# 08_Parallel_operation.net
KiCad netlist of a schematic drawn in Altium Designer
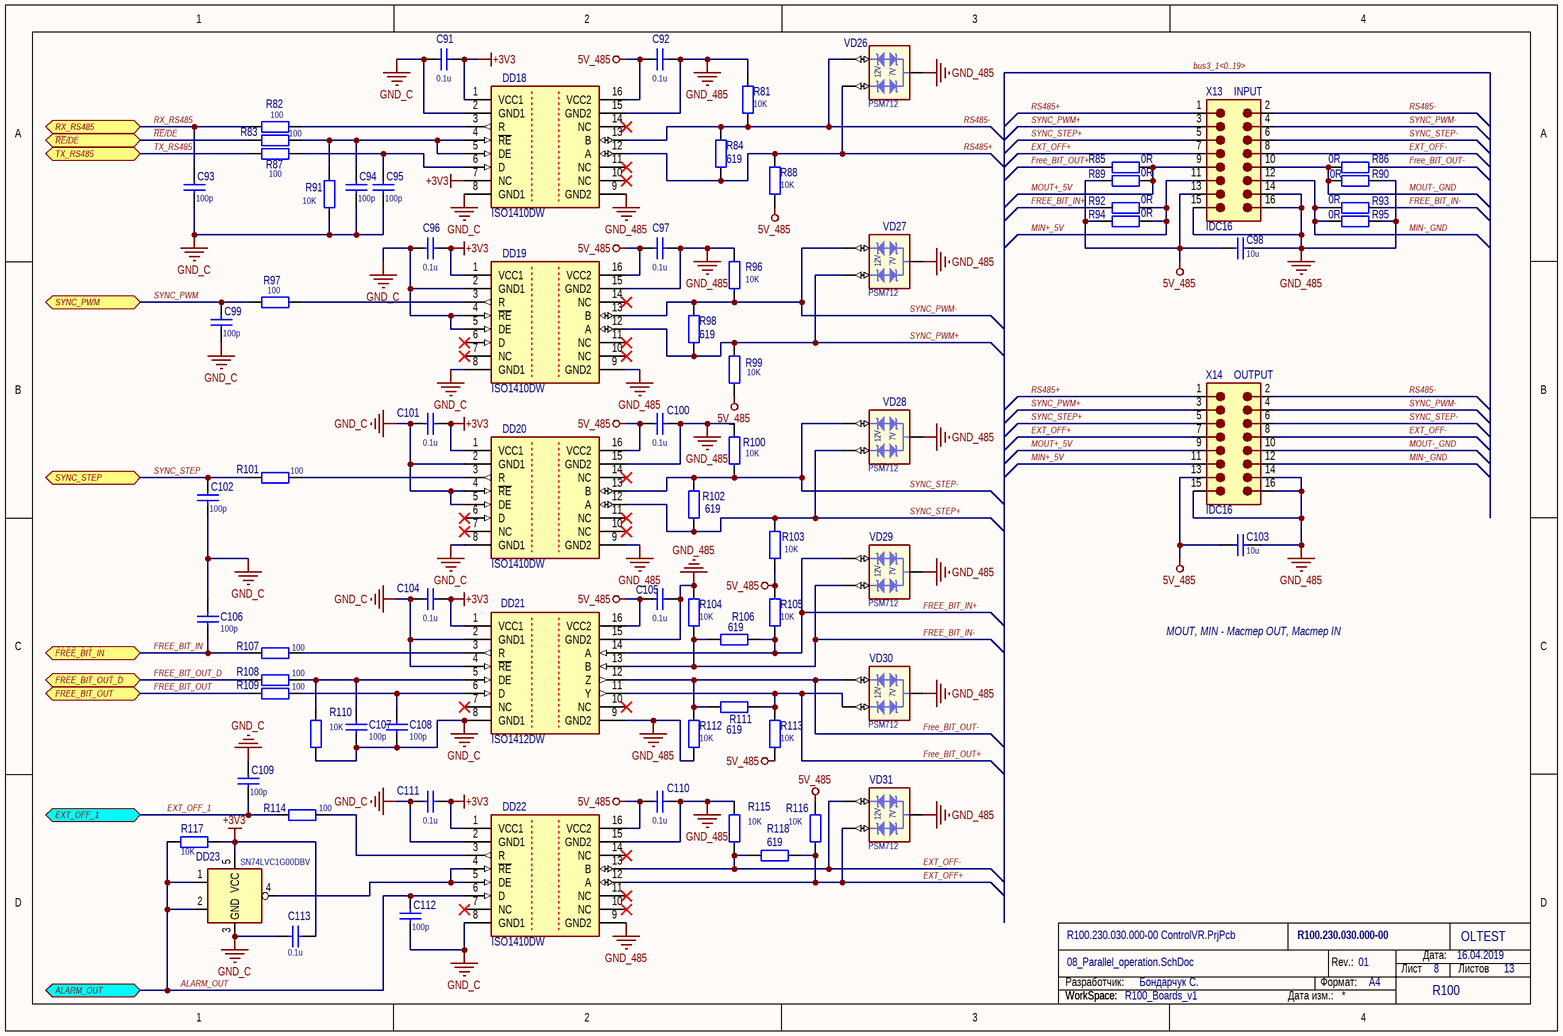
[diagram p0: 08_Parallel_operation.SchDoc]

(export (version "E")
  (design (tool "Eeschema 10.0.6"))
  (components
    (comp (ref "C91")
      (value "0.1u")
      (footprint "mainLib:SMD_C_0603")
      (description "SMD C 0603 MURATA 50V 10% X7R")
      (fields (field (name "PARTNUMBER") "GRM188R71H104K") (field (name "MANUFACTURER") "MURATA"))
      (libsource (lib "mainRCLib") (part "C0603 0.1u 50V 10%"))
    )
    (comp (ref "C92")
      (value "0.1u")
      (footprint "mainLib:SMD_C_0603")
      (description "SMD C 0603 MURATA 50V 10% X7R")
      (fields (field (name "PARTNUMBER") "GRM188R71H104K") (field (name "MANUFACTURER") "MURATA"))
      (libsource (lib "mainRCLib") (part "C0603 0.1u 50V 10%"))
    )
    (comp (ref "C93")
      (value "100p")
      (footprint "mainLib:SMD_C_0603")
      (description "SMD C 0603 MURATA 100V 5% NP0")
      (fields (field (name "PARTNUMBER") "GRM1885C2A101JA01") (field (name "MANUFACTURER") "MURATA"))
      (libsource (lib "mainRCLib") (part "C0603 100p 100V 5%"))
    )
    (comp (ref "C94")
      (value "100p")
      (footprint "mainLib:SMD_C_0603")
      (description "SMD C 0603 MURATA 100V 5% NP0")
      (fields (field (name "PARTNUMBER") "GRM1885C2A101JA01") (field (name "MANUFACTURER") "MURATA"))
      (libsource (lib "mainRCLib") (part "C0603 100p 100V 5%"))
    )
    (comp (ref "C95")
      (value "100p")
      (footprint "mainLib:SMD_C_0603")
      (description "SMD C 0603 MURATA 100V 5% NP0")
      (fields (field (name "PARTNUMBER") "GRM1885C2A101JA01") (field (name "MANUFACTURER") "MURATA"))
      (libsource (lib "mainRCLib") (part "C0603 100p 100V 5%"))
    )
    (comp (ref "C96")
      (value "0.1u")
      (footprint "mainLib:SMD_C_0603")
      (description "SMD C 0603 MURATA 50V 10% X7R")
      (fields (field (name "PARTNUMBER") "GRM188R71H104K") (field (name "MANUFACTURER") "MURATA"))
      (libsource (lib "mainRCLib") (part "C0603 0.1u 50V 10%"))
    )
    (comp (ref "C97")
      (value "0.1u")
      (footprint "mainLib:SMD_C_0603")
      (description "SMD C 0603 MURATA 50V 10% X7R")
      (fields (field (name "PARTNUMBER") "GRM188R71H104K") (field (name "MANUFACTURER") "MURATA"))
      (libsource (lib "mainRCLib") (part "C0603 0.1u 50V 10%"))
    )
    (comp (ref "C98")
      (value "10u")
      (footprint "mainLib:SMD_C_1206")
      (description "SMD C 1206 MURATA 25V 20% X5R")
      (fields (field (name "PARTNUMBER") "GRM31MR61E106M") (field (name "MANUFACTURER") "MURATA"))
      (libsource (lib "mainRCLib") (part "C1206 10u 25V 20%"))
    )
    (comp (ref "C99")
      (value "100p")
      (footprint "mainLib:SMD_C_0603")
      (description "SMD C 0603 MURATA 100V 5% NP0")
      (fields (field (name "PARTNUMBER") "GRM1885C2A101JA01") (field (name "MANUFACTURER") "MURATA"))
      (libsource (lib "mainRCLib") (part "C0603 100p 100V 5%"))
    )
    (comp (ref "C100")
      (value "0.1u")
      (footprint "mainLib:SMD_C_0603")
      (description "SMD C 0603 MURATA 50V 10% X7R")
      (fields (field (name "PARTNUMBER") "GRM188R71H104K") (field (name "MANUFACTURER") "MURATA"))
      (libsource (lib "mainRCLib") (part "C0603 0.1u 50V 10%"))
    )
    (comp (ref "C101")
      (value "0.1u")
      (footprint "mainLib:SMD_C_0603")
      (description "SMD C 0603 MURATA 50V 10% X7R")
      (fields (field (name "PARTNUMBER") "GRM188R71H104K") (field (name "MANUFACTURER") "MURATA"))
      (libsource (lib "mainRCLib") (part "C0603 0.1u 50V 10%"))
    )
    (comp (ref "C102")
      (value "100p")
      (footprint "mainLib:SMD_C_0603")
      (description "SMD C 0603 MURATA 100V 5% NP0")
      (fields (field (name "PARTNUMBER") "GRM1885C2A101JA01") (field (name "MANUFACTURER") "MURATA"))
      (libsource (lib "mainRCLib") (part "C0603 100p 100V 5%"))
    )
    (comp (ref "C103")
      (value "10u")
      (footprint "mainLib:SMD_C_1206")
      (description "SMD C 1206 MURATA 25V 20% X5R")
      (fields (field (name "PARTNUMBER") "GRM31MR61E106M") (field (name "MANUFACTURER") "MURATA"))
      (libsource (lib "mainRCLib") (part "C1206 10u 25V 20%"))
    )
    (comp (ref "C104")
      (value "0.1u")
      (footprint "mainLib:SMD_C_0603")
      (description "SMD C 0603 MURATA 50V 10% X7R")
      (fields (field (name "PARTNUMBER") "GRM188R71H104K") (field (name "MANUFACTURER") "MURATA"))
      (libsource (lib "mainRCLib") (part "C0603 0.1u 50V 10%"))
    )
    (comp (ref "C105")
      (value "0.1u")
      (footprint "mainLib:SMD_C_0603")
      (description "SMD C 0603 MURATA 50V 10% X7R")
      (fields (field (name "PARTNUMBER") "GRM188R71H104K") (field (name "MANUFACTURER") "MURATA"))
      (libsource (lib "mainRCLib") (part "C0603 0.1u 50V 10%"))
    )
    (comp (ref "C106")
      (value "100p")
      (footprint "mainLib:SMD_C_0603")
      (description "SMD C 0603 MURATA 100V 5% NP0")
      (fields (field (name "PARTNUMBER") "GRM1885C2A101JA01") (field (name "MANUFACTURER") "MURATA"))
      (libsource (lib "mainRCLib") (part "C0603 100p 100V 5%"))
    )
    (comp (ref "C107")
      (value "100p")
      (footprint "mainLib:SMD_C_0603")
      (description "SMD C 0603 MURATA 100V 5% NP0")
      (fields (field (name "PARTNUMBER") "GRM1885C2A101JA01") (field (name "MANUFACTURER") "MURATA"))
      (libsource (lib "mainRCLib") (part "C0603 100p 100V 5%"))
    )
    (comp (ref "C108")
      (value "100p")
      (footprint "mainLib:SMD_C_0603")
      (description "SMD C 0603 MURATA 100V 5% NP0")
      (fields (field (name "PARTNUMBER") "GRM1885C2A101JA01") (field (name "MANUFACTURER") "MURATA"))
      (libsource (lib "mainRCLib") (part "C0603 100p 100V 5%"))
    )
    (comp (ref "C109")
      (value "100p")
      (footprint "mainLib:SMD_C_0603")
      (description "SMD C 0603 MURATA 100V 5% NP0")
      (fields (field (name "PARTNUMBER") "GRM1885C2A101JA01") (field (name "MANUFACTURER") "MURATA"))
      (libsource (lib "mainRCLib") (part "C0603 100p 100V 5%"))
    )
    (comp (ref "C110")
      (value "0.1u")
      (footprint "mainLib:SMD_C_0603")
      (description "SMD C 0603 MURATA 50V 10% X7R")
      (fields (field (name "PARTNUMBER") "GRM188R71H104K") (field (name "MANUFACTURER") "MURATA"))
      (libsource (lib "mainRCLib") (part "C0603 0.1u 50V 10%"))
    )
    (comp (ref "C111")
      (value "0.1u")
      (footprint "mainLib:SMD_C_0603")
      (description "SMD C 0603 MURATA 50V 10% X7R")
      (fields (field (name "PARTNUMBER") "GRM188R71H104K") (field (name "MANUFACTURER") "MURATA"))
      (libsource (lib "mainRCLib") (part "C0603 0.1u 50V 10%"))
    )
    (comp (ref "C112")
      (value "100p")
      (footprint "mainLib:SMD_C_0603")
      (description "SMD C 0603 MURATA 100V 5% NP0")
      (fields (field (name "PARTNUMBER") "GRM1885C2A101JA01") (field (name "MANUFACTURER") "MURATA"))
      (libsource (lib "mainRCLib") (part "C0603 100p 100V 5%"))
    )
    (comp (ref "C113")
      (value "0.1u")
      (footprint "mainLib:SMD_C_0603")
      (description "SMD C 0603 MURATA 50V 10% X7R")
      (fields (field (name "PARTNUMBER") "GRM188R71H104K") (field (name "MANUFACTURER") "MURATA"))
      (libsource (lib "mainRCLib") (part "C0603 0.1u 50V 10%"))
    )
    (comp (ref "DD18")
      (value "ISO1410DW")
      (footprint "mainLib:SOIC127P1030X265-16M")
      (description "Isolated, Half-Dupl RS-485 Transiver")
      (fields (field (name "MANUFACTURER") "Texas Instrument"))
      (libsource (lib "mainLib") (part "ISO1410DW"))
    )
    (comp (ref "DD19")
      (value "ISO1410DW")
      (footprint "mainLib:SOIC127P1030X265-16M")
      (description "Isolated, Half-Dupl RS-485 Transiver")
      (fields (field (name "MANUFACTURER") "Texas Instrument"))
      (libsource (lib "mainLib") (part "ISO1410DW"))
    )
    (comp (ref "DD20")
      (value "ISO1410DW")
      (footprint "mainLib:SOIC127P1030X265-16M")
      (description "Isolated, Half-Dupl RS-485 Transiver")
      (fields (field (name "MANUFACTURER") "Texas Instrument"))
      (libsource (lib "mainLib") (part "ISO1410DW"))
    )
    (comp (ref "DD21")
      (value "ISO1412DW")
      (footprint "mainLib:SOIC127P1030X265-16M")
      (description "Isolated, Full-Dupl RS-485 Transiver")
      (fields (field (name "MANUFACTURER") "Texas Instrument"))
      (libsource (lib "mainLib") (part "ISO1412DW"))
    )
    (comp (ref "DD22")
      (value "ISO1410DW")
      (footprint "mainLib:SOIC127P1030X265-16M")
      (description "Isolated, Half-Dupl RS-485 Transiver")
      (fields (field (name "MANUFACTURER") "Texas Instrument"))
      (libsource (lib "mainLib") (part "ISO1410DW"))
    )
    (comp (ref "DD23")
      (value "SN74LVC1G00DBV")
      (footprint "mainLib:SOT-23(DBV)")
      (description "2-in NAND")
      (fields (field (name "MANUFACTURER") "Texas Instruments"))
      (libsource (lib "mainLib") (part "SN74LVC1G00DBV"))
    )
    (comp (ref "R81")
      (value "10K")
      (footprint "SMD_R_0603")
      (description "SMD R 0603 VISHAY 0.1W 75V 1% 100ppm")
      (fields (field (name "PARTNUMBER") "CRCW060310K0FK") (field (name "MANUFACTURER") "VISHAY"))
      (libsource (lib "") (part "R0603 10К 1%_1"))
    )
    (comp (ref "R82")
      (value "100")
      (footprint "SMD_R_0603")
      (description "SMD R 0603 VISHAY 0.1W 75V 1% 100ppm")
      (fields (field (name "PARTNUMBER") "CRCW0603100RFK") (field (name "MANUFACTURER") "VISHAY"))
      (libsource (lib "mainRCLib") (part "R0603 100 1%"))
    )
    (comp (ref "R83")
      (value "100")
      (footprint "SMD_R_0603")
      (description "SMD R 0603 VISHAY 0.1W 75V 1% 100ppm")
      (fields (field (name "PARTNUMBER") "CRCW0603100RFK") (field (name "MANUFACTURER") "VISHAY"))
      (libsource (lib "mainRCLib") (part "R0603 100 1%"))
    )
    (comp (ref "R84")
      (value "619")
      (footprint "mainLib:SMD_R_0603")
      (description "SMD 0603 VISHAY 0.1W 75V 1% 100ppm")
      (fields (field (name "PARTNUMBER") "CRCW0603619RFK") (field (name "MANUFACTURER") "VISHAY"))
      (libsource (lib "mainRCLib") (part "R0603 619 1%"))
    )
    (comp (ref "R85")
      (value "0R")
      (footprint "mainLib:SMD_R_0603")
      (description "SMD R 0603 VISHAY 0.1W 75V 1% 100ppm")
      (fields (field (name "PARTNUMBER") "CRCW06030000Z0") (field (name "MANUFACTURER") "VISHAY"))
      (libsource (lib "mainRCLib") (part "R0603 0R 1%"))
    )
    (comp (ref "R86")
      (value "0R")
      (footprint "mainLib:SMD_R_0603")
      (description "SMD R 0603 VISHAY 0.1W 75V 1% 100ppm")
      (fields (field (name "PARTNUMBER") "CRCW06030000Z0") (field (name "MANUFACTURER") "VISHAY"))
      (libsource (lib "mainRCLib") (part "R0603 0R 1%"))
    )
    (comp (ref "R87")
      (value "100")
      (footprint "SMD_R_0603")
      (description "SMD R 0603 VISHAY 0.1W 75V 1% 100ppm")
      (fields (field (name "PARTNUMBER") "CRCW0603100RFK") (field (name "MANUFACTURER") "VISHAY"))
      (libsource (lib "mainRCLib") (part "R0603 100 1%"))
    )
    (comp (ref "R88")
      (value "10K")
      (footprint "SMD_R_0603")
      (description "SMD R 0603 VISHAY 0.1W 75V 1% 100ppm")
      (fields (field (name "PARTNUMBER") "CRCW060310K0FK") (field (name "MANUFACTURER") "VISHAY"))
      (libsource (lib "mainRCLib") (part "R0603 10К 1%"))
    )
    (comp (ref "R89")
      (value "0R")
      (footprint "mainLib:SMD_R_0603")
      (description "SMD R 0603 VISHAY 0.1W 75V 1% 100ppm")
      (fields (field (name "PARTNUMBER") "CRCW06030000Z0") (field (name "MANUFACTURER") "VISHAY"))
      (libsource (lib "mainRCLib") (part "R0603 0R 1%"))
    )
    (comp (ref "R90")
      (value "0R")
      (footprint "mainLib:SMD_R_0603")
      (description "SMD R 0603 VISHAY 0.1W 75V 1% 100ppm")
      (fields (field (name "PARTNUMBER") "CRCW06030000Z0") (field (name "MANUFACTURER") "VISHAY"))
      (libsource (lib "mainRCLib") (part "R0603 0R 1%"))
    )
    (comp (ref "R91")
      (value "10K")
      (footprint "SMD_R_0603")
      (description "SMD R 0603 VISHAY 0.1W 75V 1% 100ppm")
      (fields (field (name "PARTNUMBER") "CRCW060310K0FK") (field (name "MANUFACTURER") "VISHAY"))
      (libsource (lib "mainRCLib") (part "R0603 10К 1%"))
    )
    (comp (ref "R92")
      (value "0R")
      (footprint "mainLib:SMD_R_0603")
      (description "SMD R 0603 VISHAY 0.1W 75V 1% 100ppm")
      (fields (field (name "PARTNUMBER") "CRCW06030000Z0") (field (name "MANUFACTURER") "VISHAY"))
      (libsource (lib "mainRCLib") (part "R0603 0R 1%"))
    )
    (comp (ref "R93")
      (value "0R")
      (footprint "mainLib:SMD_R_0603")
      (description "SMD R 0603 VISHAY 0.1W 75V 1% 100ppm")
      (fields (field (name "PARTNUMBER") "CRCW06030000Z0") (field (name "MANUFACTURER") "VISHAY"))
      (libsource (lib "mainRCLib") (part "R0603 0R 1%"))
    )
    (comp (ref "R94")
      (value "0R")
      (footprint "mainLib:SMD_R_0603")
      (description "SMD R 0603 VISHAY 0.1W 75V 1% 100ppm")
      (fields (field (name "PARTNUMBER") "CRCW06030000Z0") (field (name "MANUFACTURER") "VISHAY"))
      (libsource (lib "mainRCLib") (part "R0603 0R 1%"))
    )
    (comp (ref "R95")
      (value "0R")
      (footprint "mainLib:SMD_R_0603")
      (description "SMD R 0603 VISHAY 0.1W 75V 1% 100ppm")
      (fields (field (name "PARTNUMBER") "CRCW06030000Z0") (field (name "MANUFACTURER") "VISHAY"))
      (libsource (lib "mainRCLib") (part "R0603 0R 1%"))
    )
    (comp (ref "R96")
      (value "10K")
      (footprint "SMD_R_0603")
      (description "SMD R 0603 VISHAY 0.1W 75V 1% 100ppm")
      (fields (field (name "PARTNUMBER") "CRCW060310K0FK") (field (name "MANUFACTURER") "VISHAY"))
      (libsource (lib "mainRCLib") (part "R0603 10К 1%"))
    )
    (comp (ref "R97")
      (value "100")
      (footprint "SMD_R_0603")
      (description "SMD R 0603 VISHAY 0.1W 75V 1% 100ppm")
      (fields (field (name "PARTNUMBER") "CRCW0603100RFK") (field (name "MANUFACTURER") "VISHAY"))
      (libsource (lib "mainRCLib") (part "R0603 100 1%"))
    )
    (comp (ref "R98")
      (value "619")
      (footprint "mainLib:SMD_R_0603")
      (description "SMD 0603 VISHAY 0.1W 75V 1% 100ppm")
      (fields (field (name "PARTNUMBER") "CRCW0603619RFK") (field (name "MANUFACTURER") "VISHAY"))
      (libsource (lib "mainRCLib") (part "R0603 619 1%"))
    )
    (comp (ref "R99")
      (value "10K")
      (footprint "SMD_R_0603")
      (description "SMD R 0603 VISHAY 0.1W 75V 1% 100ppm")
      (fields (field (name "PARTNUMBER") "CRCW060310K0FK") (field (name "MANUFACTURER") "VISHAY"))
      (libsource (lib "mainRCLib") (part "R0603 10К 1%"))
    )
    (comp (ref "R100")
      (value "10K")
      (footprint "SMD_R_0603")
      (description "SMD R 0603 VISHAY 0.1W 75V 1% 100ppm")
      (fields (field (name "PARTNUMBER") "CRCW060310K0FK") (field (name "MANUFACTURER") "VISHAY"))
      (libsource (lib "mainRCLib") (part "R0603 10К 1%"))
    )
    (comp (ref "R101")
      (value "100")
      (footprint "SMD_R_0603")
      (description "SMD R 0603 VISHAY 0.1W 75V 1% 100ppm")
      (fields (field (name "PARTNUMBER") "CRCW0603100RFK") (field (name "MANUFACTURER") "VISHAY"))
      (libsource (lib "mainRCLib") (part "R0603 100 1%"))
    )
    (comp (ref "R102")
      (value "619")
      (footprint "mainLib:SMD_R_0603")
      (description "SMD 0603 VISHAY 0.1W 75V 1% 100ppm")
      (fields (field (name "PARTNUMBER") "CRCW0603619RFK") (field (name "MANUFACTURER") "VISHAY"))
      (libsource (lib "mainRCLib") (part "R0603 619 1%"))
    )
    (comp (ref "R103")
      (value "10K")
      (footprint "SMD_R_0603")
      (description "SMD R 0603 VISHAY 0.1W 75V 1% 100ppm")
      (fields (field (name "PARTNUMBER") "CRCW060310K0FK") (field (name "MANUFACTURER") "VISHAY"))
      (libsource (lib "mainRCLib") (part "R0603 10К 1%"))
    )
    (comp (ref "R104")
      (value "10K")
      (footprint "SMD_R_0603")
      (description "SMD R 0603 VISHAY 0.1W 75V 1% 100ppm")
      (fields (field (name "PARTNUMBER") "CRCW060310K0FK") (field (name "MANUFACTURER") "VISHAY"))
      (libsource (lib "mainRCLib") (part "R0603 10К 1%"))
    )
    (comp (ref "R105")
      (value "10K")
      (footprint "SMD_R_0603")
      (description "SMD R 0603 VISHAY 0.1W 75V 1% 100ppm")
      (fields (field (name "PARTNUMBER") "CRCW060310K0FK") (field (name "MANUFACTURER") "VISHAY"))
      (libsource (lib "mainRCLib") (part "R0603 10К 1%"))
    )
    (comp (ref "R106")
      (value "619")
      (footprint "mainLib:SMD_R_0603")
      (description "SMD 0603 VISHAY 0.1W 75V 1% 100ppm")
      (fields (field (name "PARTNUMBER") "CRCW0603619RFK") (field (name "MANUFACTURER") "VISHAY"))
      (libsource (lib "") (part "R0603 619 1%_1"))
    )
    (comp (ref "R107")
      (value "100")
      (footprint "SMD_R_0603")
      (description "SMD R 0603 VISHAY 0.1W 75V 1% 100ppm")
      (fields (field (name "PARTNUMBER") "CRCW0603100RFK") (field (name "MANUFACTURER") "VISHAY"))
      (libsource (lib "mainRCLib") (part "R0603 100 1%"))
    )
    (comp (ref "R108")
      (value "100")
      (footprint "SMD_R_0603")
      (description "SMD R 0603 VISHAY 0.1W 75V 1% 100ppm")
      (fields (field (name "PARTNUMBER") "CRCW0603100RFK") (field (name "MANUFACTURER") "VISHAY"))
      (libsource (lib "mainRCLib") (part "R0603 100 1%"))
    )
    (comp (ref "R109")
      (value "100")
      (footprint "SMD_R_0603")
      (description "SMD R 0603 VISHAY 0.1W 75V 1% 100ppm")
      (fields (field (name "PARTNUMBER") "CRCW0603100RFK") (field (name "MANUFACTURER") "VISHAY"))
      (libsource (lib "mainRCLib") (part "R0603 100 1%"))
    )
    (comp (ref "R110")
      (value "10K")
      (footprint "SMD_R_0603")
      (description "SMD R 0603 VISHAY 0.1W 75V 1% 100ppm")
      (fields (field (name "PARTNUMBER") "CRCW060310K0FK") (field (name "MANUFACTURER") "VISHAY"))
      (libsource (lib "mainRCLib") (part "R0603 10К 1%"))
    )
    (comp (ref "R111")
      (value "619")
      (footprint "mainLib:SMD_R_0603")
      (description "SMD 0603 VISHAY 0.1W 75V 1% 100ppm")
      (fields (field (name "PARTNUMBER") "CRCW0603619RFK") (field (name "MANUFACTURER") "VISHAY"))
      (libsource (lib "") (part "R0603 619 1%_1"))
    )
    (comp (ref "R112")
      (value "10K")
      (footprint "SMD_R_0603")
      (description "SMD R 0603 VISHAY 0.1W 75V 1% 100ppm")
      (fields (field (name "PARTNUMBER") "CRCW060310K0FK") (field (name "MANUFACTURER") "VISHAY"))
      (libsource (lib "mainRCLib") (part "R0603 10К 1%"))
    )
    (comp (ref "R113")
      (value "10K")
      (footprint "SMD_R_0603")
      (description "SMD R 0603 VISHAY 0.1W 75V 1% 100ppm")
      (fields (field (name "PARTNUMBER") "CRCW060310K0FK") (field (name "MANUFACTURER") "VISHAY"))
      (libsource (lib "mainRCLib") (part "R0603 10К 1%"))
    )
    (comp (ref "R114")
      (value "100")
      (footprint "SMD_R_0603")
      (description "SMD R 0603 VISHAY 0.1W 75V 1% 100ppm")
      (fields (field (name "PARTNUMBER") "CRCW0603100RFK") (field (name "MANUFACTURER") "VISHAY"))
      (libsource (lib "mainRCLib") (part "R0603 100 1%"))
    )
    (comp (ref "R115")
      (value "10K")
      (footprint "SMD_R_0603")
      (description "SMD R 0603 VISHAY 0.1W 75V 1% 100ppm")
      (fields (field (name "PARTNUMBER") "CRCW060310K0FK") (field (name "MANUFACTURER") "VISHAY"))
      (libsource (lib "mainRCLib") (part "R0603 10К 1%"))
    )
    (comp (ref "R116")
      (value "10K")
      (footprint "SMD_R_0603")
      (description "SMD R 0603 VISHAY 0.1W 75V 1% 100ppm")
      (fields (field (name "PARTNUMBER") "CRCW060310K0FK") (field (name "MANUFACTURER") "VISHAY"))
      (libsource (lib "mainRCLib") (part "R0603 10К 1%"))
    )
    (comp (ref "R117")
      (value "10K")
      (footprint "SMD_R_0603")
      (description "SMD R 0603 VISHAY 0.1W 75V 1% 100ppm")
      (fields (field (name "PARTNUMBER") "CRCW060310K0FK") (field (name "MANUFACTURER") "VISHAY"))
      (libsource (lib "") (part "R0603 10К 1%_2"))
    )
    (comp (ref "R118")
      (value "619")
      (footprint "mainLib:SMD_R_0603")
      (description "SMD 0603 VISHAY 0.1W 75V 1% 100ppm")
      (fields (field (name "PARTNUMBER") "CRCW0603619RFK") (field (name "MANUFACTURER") "VISHAY"))
      (libsource (lib "") (part "R0603 619 1%_1"))
    )
    (comp (ref "VD26")
      (value "PSM712")
      (footprint "mainLib:SOT23-3")
      (description "ASYMMETRICAL DATA LINE PROTECTOR")
      (fields (field (name "MANUFACTURER") "Protec Devices"))
      (libsource (lib "mainLib") (part "PSM712"))
    )
    (comp (ref "VD27")
      (value "PSM712")
      (footprint "mainLib:SOT23-3")
      (description "ASYMMETRICAL DATA LINE PROTECTOR")
      (fields (field (name "MANUFACTURER") "Protec Devices"))
      (libsource (lib "mainLib") (part "PSM712"))
    )
    (comp (ref "VD28")
      (value "PSM712")
      (footprint "mainLib:SOT23-3")
      (description "ASYMMETRICAL DATA LINE PROTECTOR")
      (fields (field (name "MANUFACTURER") "Protec Devices"))
      (libsource (lib "mainLib") (part "PSM712"))
    )
    (comp (ref "VD29")
      (value "PSM712")
      (footprint "mainLib:SOT23-3")
      (description "ASYMMETRICAL DATA LINE PROTECTOR")
      (fields (field (name "MANUFACTURER") "Protec Devices"))
      (libsource (lib "mainLib") (part "PSM712"))
    )
    (comp (ref "VD30")
      (value "PSM712")
      (footprint "mainLib:SOT23-3")
      (description "ASYMMETRICAL DATA LINE PROTECTOR")
      (fields (field (name "MANUFACTURER") "Protec Devices"))
      (libsource (lib "mainLib") (part "PSM712"))
    )
    (comp (ref "VD31")
      (value "PSM712")
      (footprint "mainLib:SOT23-3")
      (description "ASYMMETRICAL DATA LINE PROTECTOR")
      (fields (field (name "MANUFACTURER") "Protec Devices"))
      (libsource (lib "mainLib") (part "PSM712"))
    )
    (comp (ref "X13")
      (value "IDC16")
      (footprint "918516x324")
      (fields (field (name "PARTNUMBER") "09 18 516 6324") (field (name "MANUFACTURER") "HARTING"))
      (libsource (lib "mainLib") (part "IDC16 324 Harting"))
    )
    (comp (ref "X14")
      (value "IDC16")
      (footprint "918516x324")
      (fields (field (name "PARTNUMBER") "09 18 516 6324") (field (name "MANUFACTURER") "HARTING"))
      (libsource (lib "mainLib") (part "IDC16 324 Harting"))
    )
  )
  (nets
    (net (code "2") (name "+3V3") (class "Default")
      (node (ref "C101") (pin "2") (pinfunction "2_2") (pintype "passive"))
      (node (ref "C104") (pin "2") (pinfunction "2_2") (pintype "passive"))
      (node (ref "C111") (pin "2") (pinfunction "2_2") (pintype "passive"))
      (node (ref "C113") (pin "1") (pinfunction "1_1") (pintype "passive"))
      (node (ref "C91") (pin "1") (pinfunction "1_1") (pintype "passive"))
      (node (ref "C96") (pin "2") (pinfunction "2_2") (pintype "passive"))
      (node (ref "DD18") (pin "1") (pinfunction "VCC1_1") (pintype "power_in"))
      (node (ref "DD18") (pin "7") (pinfunction "NC_7") (pintype "power_in"))
      (node (ref "DD19") (pin "1") (pinfunction "VCC1_1") (pintype "power_in"))
      (node (ref "DD20") (pin "1") (pinfunction "VCC1_1") (pintype "power_in"))
      (node (ref "DD21") (pin "1") (pinfunction "VCC1_1") (pintype "power_in"))
      (node (ref "DD22") (pin "1") (pinfunction "VCC1_1") (pintype "power_in"))
      (node (ref "DD23") (pin "5") (pinfunction "VCC_5") (pintype "passive"))
      (node (ref "R117") (pin "1") (pinfunction "1_1") (pintype "passive"))
    )
    (net (code "3") (name "/ALARM_OUT") (class "Default")
      (node (ref "C112") (pin "2") (pinfunction "2_2") (pintype "passive"))
      (node (ref "DD22") (pin "6") (pinfunction "D_6") (pintype "input"))
      (node (ref "DD23") (pin "1") (pintype "passive"))
      (node (ref "DD23") (pin "2") (pintype "passive"))
      (node (ref "R117") (pin "2") (pinfunction "2_2") (pintype "passive"))
    )
    (net (code "4") (name "/EXT_OFF+") (class "Default")
      (node (ref "DD22") (pin "12") (pinfunction "A_12") (pintype "bidirectional"))
      (node (ref "R116") (pin "1") (pinfunction "1_1") (pintype "passive"))
      (node (ref "R118") (pin "1") (pinfunction "1_1") (pintype "passive"))
      (node (ref "VD31") (pin "2") (pinfunction "I/O2_2") (pintype "bidirectional"))
      (node (ref "X13") (pin "7") (pinfunction "7_7") (pintype "passive"))
      (node (ref "X14") (pin "7") (pinfunction "7_7") (pintype "passive"))
    )
    (net (code "5") (name "/EXT_OFF-") (class "Default")
      (node (ref "DD22") (pin "13") (pinfunction "B_13") (pintype "bidirectional"))
      (node (ref "R115") (pin "1") (pinfunction "1_1") (pintype "passive"))
      (node (ref "R118") (pin "2") (pinfunction "2_2") (pintype "passive"))
      (node (ref "VD31") (pin "1") (pinfunction "I/O1_1") (pintype "bidirectional"))
      (node (ref "X13") (pin "8") (pinfunction "8_8") (pintype "passive"))
      (node (ref "X14") (pin "8") (pinfunction "8_8") (pintype "passive"))
    )
    (net (code "6") (name "/EXT_OFF_1") (class "Default")
      (node (ref "C109") (pin "1") (pinfunction "1_1") (pintype "passive"))
      (node (ref "R114") (pin "1") (pinfunction "1_1") (pintype "passive"))
    )
    (net (code "7") (name "/FREE_BIT_IN") (class "Default")
      (node (ref "C106") (pin "2") (pinfunction "2_2") (pintype "passive"))
      (node (ref "R107") (pin "1") (pinfunction "1_1") (pintype "passive"))
    )
    (net (code "8") (name "/FREE_BIT_IN+") (class "Default")
      (node (ref "DD21") (pin "14") (pinfunction "A_14") (pintype "input"))
      (node (ref "R105") (pin "1") (pinfunction "1_1") (pintype "passive"))
      (node (ref "R106") (pin "1") (pinfunction "1_1") (pintype "passive"))
      (node (ref "R92") (pin "1") (pinfunction "1_1") (pintype "passive"))
      (node (ref "VD29") (pin "1") (pinfunction "I/O1_1") (pintype "bidirectional"))
    )
    (net (code "9") (name "/FREE_BIT_IN-") (class "Default")
      (node (ref "DD21") (pin "13") (pinfunction "B_13") (pintype "input"))
      (node (ref "R104") (pin "1") (pinfunction "1_1") (pintype "passive"))
      (node (ref "R106") (pin "2") (pinfunction "2_2") (pintype "passive"))
      (node (ref "R93") (pin "2") (pinfunction "2_2") (pintype "passive"))
      (node (ref "VD29") (pin "2") (pinfunction "I/O2_2") (pintype "bidirectional"))
    )
    (net (code "10") (name "/FREE_BIT_OUT") (class "Default")
      (node (ref "R109") (pin "1") (pinfunction "1_1") (pintype "passive"))
    )
    (net (code "11") (name "/FREE_BIT_OUT_D") (class "Default")
      (node (ref "R108") (pin "1") (pinfunction "1_1") (pintype "passive"))
    )
    (net (code "12") (name "/Free_BIT_OUT+") (class "Default")
      (node (ref "DD21") (pin "11") (pinfunction "Y_11") (pintype "output"))
      (node (ref "R111") (pin "1") (pinfunction "1_1") (pintype "passive"))
      (node (ref "R113") (pin "2") (pinfunction "2_2") (pintype "passive"))
      (node (ref "R85") (pin "1") (pinfunction "1_1") (pintype "passive"))
      (node (ref "VD30") (pin "2") (pinfunction "I/O2_2") (pintype "bidirectional"))
    )
    (net (code "13") (name "/Free_BIT_OUT-") (class "Default")
      (node (ref "DD21") (pin "12") (pinfunction "Z_12") (pintype "output"))
      (node (ref "R111") (pin "2") (pinfunction "2_2") (pintype "passive"))
      (node (ref "R112") (pin "2") (pinfunction "2_2") (pintype "passive"))
      (node (ref "R86") (pin "2") (pinfunction "2_2") (pintype "passive"))
      (node (ref "VD30") (pin "1") (pinfunction "I/O1_1") (pintype "bidirectional"))
    )
    (net (code "14") (name "/MIN+_5V") (class "Default")
      (node (ref "R92") (pin "2") (pinfunction "2_2") (pintype "passive"))
      (node (ref "R94") (pin "2") (pinfunction "2_2") (pintype "passive"))
      (node (ref "X13") (pin "11") (pinfunction "11_11") (pintype "passive"))
      (node (ref "X14") (pin "11") (pinfunction "11_11") (pintype "passive"))
    )
    (net (code "15") (name "/MIN-_GND") (class "Default")
      (node (ref "R93") (pin "1") (pinfunction "1_1") (pintype "passive"))
      (node (ref "R95") (pin "1") (pinfunction "1_1") (pintype "passive"))
      (node (ref "X13") (pin "12") (pinfunction "12_12") (pintype "passive"))
      (node (ref "X14") (pin "12") (pinfunction "12_12") (pintype "passive"))
    )
    (net (code "16") (name "/MOUT+_5V") (class "Default")
      (node (ref "R85") (pin "2") (pinfunction "2_2") (pintype "passive"))
      (node (ref "R89") (pin "2") (pinfunction "2_2") (pintype "passive"))
      (node (ref "X13") (pin "9") (pinfunction "9_9") (pintype "passive"))
      (node (ref "X14") (pin "9") (pinfunction "9_9") (pintype "passive"))
    )
    (net (code "17") (name "/MOUT-_GND") (class "Default")
      (node (ref "R86") (pin "1") (pinfunction "1_1") (pintype "passive"))
      (node (ref "R90") (pin "1") (pinfunction "1_1") (pintype "passive"))
      (node (ref "X13") (pin "10") (pinfunction "10_10") (pintype "passive"))
      (node (ref "X14") (pin "10") (pinfunction "10_10") (pintype "passive"))
    )
    (net (code "18") (name "/RS485+") (class "Default")
      (node (ref "DD18") (pin "12") (pinfunction "A_12") (pintype "bidirectional"))
      (node (ref "R84") (pin "1") (pinfunction "1_1") (pintype "passive"))
      (node (ref "R88") (pin "2") (pinfunction "2_2") (pintype "passive"))
      (node (ref "VD26") (pin "2") (pinfunction "I/O2_2") (pintype "bidirectional"))
      (node (ref "X13") (pin "1") (pinfunction "1_1") (pintype "passive"))
      (node (ref "X14") (pin "1") (pinfunction "1_1") (pintype "passive"))
    )
    (net (code "19") (name "/RS485-") (class "Default")
      (node (ref "DD18") (pin "13") (pinfunction "B_13") (pintype "bidirectional"))
      (node (ref "R81") (pin "2") (pinfunction "2_2") (pintype "passive"))
      (node (ref "R84") (pin "2") (pinfunction "2_2") (pintype "passive"))
      (node (ref "VD26") (pin "1") (pinfunction "I/O1_1") (pintype "bidirectional"))
      (node (ref "X13") (pin "2") (pinfunction "2_2") (pintype "passive"))
      (node (ref "X14") (pin "2") (pinfunction "2_2") (pintype "passive"))
    )
    (net (code "20") (name "/RX_RS485") (class "Default")
      (node (ref "C93") (pin "2") (pinfunction "2_2") (pintype "passive"))
      (node (ref "R82") (pin "1") (pinfunction "1_1") (pintype "passive"))
    )
    (net (code "21") (name "/SYNC_PWM") (class "Default")
      (node (ref "C99") (pin "2") (pinfunction "2_2") (pintype "passive"))
      (node (ref "R97") (pin "1") (pinfunction "1_1") (pintype "passive"))
    )
    (net (code "22") (name "/SYNC_PWM+") (class "Default")
      (node (ref "DD19") (pin "12") (pinfunction "A_12") (pintype "bidirectional"))
      (node (ref "R98") (pin "1") (pinfunction "1_1") (pintype "passive"))
      (node (ref "R99") (pin "2") (pinfunction "2_2") (pintype "passive"))
      (node (ref "VD27") (pin "2") (pinfunction "I/O2_2") (pintype "bidirectional"))
      (node (ref "X13") (pin "3") (pinfunction "3_3") (pintype "passive"))
      (node (ref "X14") (pin "3") (pinfunction "3_3") (pintype "passive"))
    )
    (net (code "23") (name "/SYNC_PWM-") (class "Default")
      (node (ref "DD19") (pin "13") (pinfunction "B_13") (pintype "bidirectional"))
      (node (ref "R96") (pin "1") (pinfunction "1_1") (pintype "passive"))
      (node (ref "R98") (pin "2") (pinfunction "2_2") (pintype "passive"))
      (node (ref "VD27") (pin "1") (pinfunction "I/O1_1") (pintype "bidirectional"))
      (node (ref "X13") (pin "4") (pinfunction "4_4") (pintype "passive"))
      (node (ref "X14") (pin "4") (pinfunction "4_4") (pintype "passive"))
    )
    (net (code "24") (name "/SYNC_STEP") (class "Default")
      (node (ref "C102") (pin "2") (pinfunction "2_2") (pintype "passive"))
      (node (ref "R101") (pin "1") (pinfunction "1_1") (pintype "passive"))
    )
    (net (code "25") (name "/SYNC_STEP+") (class "Default")
      (node (ref "DD20") (pin "12") (pinfunction "A_12") (pintype "bidirectional"))
      (node (ref "R102") (pin "1") (pinfunction "1_1") (pintype "passive"))
      (node (ref "R103") (pin "2") (pinfunction "2_2") (pintype "passive"))
      (node (ref "VD28") (pin "2") (pinfunction "I/O2_2") (pintype "bidirectional"))
      (node (ref "X13") (pin "5") (pinfunction "5_5") (pintype "passive"))
      (node (ref "X14") (pin "5") (pinfunction "5_5") (pintype "passive"))
    )
    (net (code "26") (name "/SYNC_STEP-") (class "Default")
      (node (ref "DD20") (pin "13") (pinfunction "B_13") (pintype "bidirectional"))
      (node (ref "R100") (pin "1") (pinfunction "1_1") (pintype "passive"))
      (node (ref "R102") (pin "2") (pinfunction "2_2") (pintype "passive"))
      (node (ref "VD28") (pin "1") (pinfunction "I/O1_1") (pintype "bidirectional"))
      (node (ref "X13") (pin "6") (pinfunction "6_6") (pintype "passive"))
      (node (ref "X14") (pin "6") (pinfunction "6_6") (pintype "passive"))
    )
    (net (code "27") (name "/TX_RS485") (class "Default")
      (node (ref "R87") (pin "1") (pinfunction "1_1") (pintype "passive"))
    )
    (net (code "29") (name "/~{RE}{slash}DE") (class "Default")
      (node (ref "R83") (pin "1") (pinfunction "1_1") (pintype "passive"))
    )
    (net (code "30") (name "5V_485") (class "Default")
      (node (ref "C100") (pin "2") (pinfunction "2_2") (pintype "passive"))
      (node (ref "C103") (pin "2") (pinfunction "2_2") (pintype "passive"))
      (node (ref "C105") (pin "2") (pinfunction "2_2") (pintype "passive"))
      (node (ref "C110") (pin "2") (pinfunction "2_2") (pintype "passive"))
      (node (ref "C92") (pin "2") (pinfunction "2_2") (pintype "passive"))
      (node (ref "C97") (pin "2") (pinfunction "2_2") (pintype "passive"))
      (node (ref "C98") (pin "2") (pinfunction "2_2") (pintype "passive"))
      (node (ref "DD18") (pin "16") (pinfunction "VCC2_16") (pintype "power_in"))
      (node (ref "DD19") (pin "16") (pinfunction "VCC2_16") (pintype "power_in"))
      (node (ref "DD20") (pin "16") (pinfunction "VCC2_16") (pintype "power_in"))
      (node (ref "DD21") (pin "16") (pinfunction "VCC2_16") (pintype "power_in"))
      (node (ref "DD22") (pin "16") (pinfunction "VCC2_16") (pintype "power_in"))
      (node (ref "R103") (pin "1") (pinfunction "1_1") (pintype "passive"))
      (node (ref "R105") (pin "2") (pinfunction "2_2") (pintype "passive"))
      (node (ref "R113") (pin "1") (pinfunction "1_1") (pintype "passive"))
      (node (ref "R116") (pin "2") (pinfunction "2_2") (pintype "passive"))
      (node (ref "R88") (pin "1") (pinfunction "1_1") (pintype "passive"))
      (node (ref "R89") (pin "1") (pinfunction "1_1") (pintype "passive"))
      (node (ref "R94") (pin "1") (pinfunction "1_1") (pintype "passive"))
      (node (ref "R99") (pin "1") (pinfunction "1_1") (pintype "passive"))
      (node (ref "X13") (pin "13") (pinfunction "13_13") (pintype "passive"))
      (node (ref "X14") (pin "13") (pinfunction "13_13") (pintype "passive"))
    )
    (net (code "31") (name "GND_485") (class "Default")
      (node (ref "C100") (pin "1") (pinfunction "1_1") (pintype "passive"))
      (node (ref "C103") (pin "1") (pinfunction "1_1") (pintype "passive"))
      (node (ref "C105") (pin "1") (pinfunction "1_1") (pintype "passive"))
      (node (ref "C110") (pin "1") (pinfunction "1_1") (pintype "passive"))
      (node (ref "C92") (pin "1") (pinfunction "1_1") (pintype "passive"))
      (node (ref "C97") (pin "1") (pinfunction "1_1") (pintype "passive"))
      (node (ref "C98") (pin "1") (pinfunction "1_1") (pintype "passive"))
      (node (ref "DD18") (pin "15") (pinfunction "GND2_15") (pintype "power_in"))
      (node (ref "DD18") (pin "9") (pinfunction "GND2_9") (pintype "passive"))
      (node (ref "DD19") (pin "15") (pinfunction "GND2_15") (pintype "power_in"))
      (node (ref "DD19") (pin "9") (pinfunction "GND2_9") (pintype "passive"))
      (node (ref "DD20") (pin "15") (pinfunction "GND2_15") (pintype "power_in"))
      (node (ref "DD20") (pin "9") (pinfunction "GND2_9") (pintype "passive"))
      (node (ref "DD21") (pin "15") (pinfunction "GND2_15") (pintype "power_in"))
      (node (ref "DD21") (pin "9") (pinfunction "GND2_9") (pintype "passive"))
      (node (ref "DD22") (pin "15") (pinfunction "GND2_15") (pintype "power_in"))
      (node (ref "DD22") (pin "9") (pinfunction "GND2_9") (pintype "passive"))
      (node (ref "R100") (pin "2") (pinfunction "2_2") (pintype "passive"))
      (node (ref "R104") (pin "2") (pinfunction "2_2") (pintype "passive"))
      (node (ref "R112") (pin "1") (pinfunction "1_1") (pintype "passive"))
      (node (ref "R115") (pin "2") (pinfunction "2_2") (pintype "passive"))
      (node (ref "R81") (pin "1") (pinfunction "1_1") (pintype "passive"))
      (node (ref "R90") (pin "2") (pinfunction "2_2") (pintype "passive"))
      (node (ref "R95") (pin "2") (pinfunction "2_2") (pintype "passive"))
      (node (ref "R96") (pin "2") (pinfunction "2_2") (pintype "passive"))
      (node (ref "VD26") (pin "3") (pinfunction "GND_3") (pintype "power_in"))
      (node (ref "VD27") (pin "3") (pinfunction "GND_3") (pintype "power_in"))
      (node (ref "VD28") (pin "3") (pinfunction "GND_3") (pintype "power_in"))
      (node (ref "VD29") (pin "3") (pinfunction "GND_3") (pintype "power_in"))
      (node (ref "VD30") (pin "3") (pinfunction "GND_3") (pintype "power_in"))
      (node (ref "VD31") (pin "3") (pinfunction "GND_3") (pintype "power_in"))
      (node (ref "X13") (pin "14") (pinfunction "14_14") (pintype "passive"))
      (node (ref "X13") (pin "15") (pinfunction "15_15") (pintype "passive"))
      (node (ref "X13") (pin "16") (pinfunction "16_16") (pintype "passive"))
      (node (ref "X14") (pin "14") (pinfunction "14_14") (pintype "passive"))
      (node (ref "X14") (pin "15") (pinfunction "15_15") (pintype "passive"))
      (node (ref "X14") (pin "16") (pinfunction "16_16") (pintype "passive"))
    )
    (net (code "32") (name "GND_C") (class "Default")
      (node (ref "C101") (pin "1") (pinfunction "1_1") (pintype "passive"))
      (node (ref "C102") (pin "1") (pinfunction "1_1") (pintype "passive"))
      (node (ref "C104") (pin "1") (pinfunction "1_1") (pintype "passive"))
      (node (ref "C106") (pin "1") (pinfunction "1_1") (pintype "passive"))
      (node (ref "C107") (pin "2") (pinfunction "2_2") (pintype "passive"))
      (node (ref "C108") (pin "2") (pinfunction "2_2") (pintype "passive"))
      (node (ref "C109") (pin "2") (pinfunction "2_2") (pintype "passive"))
      (node (ref "C111") (pin "1") (pinfunction "1_1") (pintype "passive"))
      (node (ref "C112") (pin "1") (pinfunction "1_1") (pintype "passive"))
      (node (ref "C113") (pin "2") (pinfunction "2_2") (pintype "passive"))
      (node (ref "C91") (pin "2") (pinfunction "2_2") (pintype "passive"))
      (node (ref "C93") (pin "1") (pinfunction "1_1") (pintype "passive"))
      (node (ref "C94") (pin "1") (pinfunction "1_1") (pintype "passive"))
      (node (ref "C95") (pin "1") (pinfunction "1_1") (pintype "passive"))
      (node (ref "C96") (pin "1") (pinfunction "1_1") (pintype "passive"))
      (node (ref "C99") (pin "1") (pinfunction "1_1") (pintype "passive"))
      (node (ref "DD18") (pin "2") (pinfunction "GND1_2") (pintype "power_in"))
      (node (ref "DD18") (pin "8") (pinfunction "GND1_8") (pintype "power_in"))
      (node (ref "DD19") (pin "2") (pinfunction "GND1_2") (pintype "power_in"))
      (node (ref "DD19") (pin "4") (pinfunction "~{RE}_4") (pintype "input"))
      (node (ref "DD19") (pin "5") (pinfunction "DE_5") (pintype "input"))
      (node (ref "DD19") (pin "8") (pinfunction "GND1_8") (pintype "power_in"))
      (node (ref "DD20") (pin "2") (pinfunction "GND1_2") (pintype "power_in"))
      (node (ref "DD20") (pin "4") (pinfunction "~{RE}_4") (pintype "input"))
      (node (ref "DD20") (pin "5") (pinfunction "DE_5") (pintype "input"))
      (node (ref "DD20") (pin "8") (pinfunction "GND1_8") (pintype "power_in"))
      (node (ref "DD21") (pin "2") (pinfunction "GND1_2") (pintype "power_in"))
      (node (ref "DD21") (pin "4") (pinfunction "~{RE}_4") (pintype "input"))
      (node (ref "DD21") (pin "8") (pinfunction "GND1_8") (pintype "power_in"))
      (node (ref "DD22") (pin "2") (pinfunction "GND1_2") (pintype "power_in"))
      (node (ref "DD22") (pin "8") (pinfunction "GND1_8") (pintype "power_in"))
      (node (ref "DD23") (pin "3") (pinfunction "GND_3") (pintype "passive"))
      (node (ref "R110") (pin "1") (pinfunction "1_1") (pintype "passive"))
      (node (ref "R91") (pin "1") (pinfunction "1_1") (pintype "passive"))
    )
    (net (code "33") (name "Net-(DD18-D)") (class "Default")
      (node (ref "C95") (pin "2") (pinfunction "2_2") (pintype "passive"))
      (node (ref "DD18") (pin "6") (pinfunction "D_6") (pintype "input"))
      (node (ref "R87") (pin "2") (pinfunction "2_2") (pintype "passive"))
    )
    (net (code "34") (name "Net-(DD18-DE)") (class "Default")
      (node (ref "C94") (pin "2") (pinfunction "2_2") (pintype "passive"))
      (node (ref "DD18") (pin "4") (pinfunction "~{RE}_4") (pintype "input"))
      (node (ref "DD18") (pin "5") (pinfunction "DE_5") (pintype "input"))
      (node (ref "R83") (pin "2") (pinfunction "2_2") (pintype "passive"))
      (node (ref "R91") (pin "2") (pinfunction "2_2") (pintype "passive"))
    )
    (net (code "35") (name "Net-(DD18-R)") (class "Default")
      (node (ref "DD18") (pin "3") (pinfunction "R_3") (pintype "output"))
      (node (ref "R82") (pin "2") (pinfunction "2_2") (pintype "passive"))
    )
    (net (code "36") (name "Net-(DD19-R)") (class "Default")
      (node (ref "DD19") (pin "3") (pinfunction "R_3") (pintype "output"))
      (node (ref "R97") (pin "2") (pinfunction "2_2") (pintype "passive"))
    )
    (net (code "37") (name "Net-(DD20-R)") (class "Default")
      (node (ref "DD20") (pin "3") (pinfunction "R_3") (pintype "output"))
      (node (ref "R101") (pin "2") (pinfunction "2_2") (pintype "passive"))
    )
    (net (code "38") (name "Net-(DD21-D)") (class "Default")
      (node (ref "C108") (pin "1") (pinfunction "1_1") (pintype "passive"))
      (node (ref "DD21") (pin "6") (pinfunction "D_6") (pintype "input"))
      (node (ref "R109") (pin "2") (pinfunction "2_2") (pintype "passive"))
    )
    (net (code "39") (name "Net-(DD21-DE)") (class "Default")
      (node (ref "C107") (pin "1") (pinfunction "1_1") (pintype "passive"))
      (node (ref "DD21") (pin "5") (pinfunction "DE_5") (pintype "input"))
      (node (ref "R108") (pin "2") (pinfunction "2_2") (pintype "passive"))
      (node (ref "R110") (pin "2") (pinfunction "2_2") (pintype "passive"))
    )
    (net (code "40") (name "Net-(DD21-R)") (class "Default")
      (node (ref "DD21") (pin "3") (pinfunction "R_3") (pintype "output"))
      (node (ref "R107") (pin "2") (pinfunction "2_2") (pintype "passive"))
    )
    (net (code "41") (name "Net-(DD22-DE)") (class "Default")
      (node (ref "DD22") (pin "4") (pinfunction "~{RE}_4") (pintype "input"))
      (node (ref "DD22") (pin "5") (pinfunction "DE_5") (pintype "input"))
      (node (ref "DD23") (pin "4") (pintype "passive"))
    )
    (net (code "42") (name "Net-(DD22-R)") (class "Default")
      (node (ref "DD22") (pin "3") (pinfunction "R_3") (pintype "output"))
      (node (ref "R114") (pin "2") (pinfunction "2_2") (pintype "passive"))
    )
    (net (code "43") (name "unconnected-(DD18-NC-Pad10)") (class "Default")
      (node (ref "DD18") (pin "10") (pinfunction "NC_10") (pintype "passive+no_connect"))
    )
    (net (code "44") (name "unconnected-(DD18-NC-Pad11)") (class "Default")
      (node (ref "DD18") (pin "11") (pinfunction "NC_11") (pintype "tri_state+no_connect"))
    )
    (net (code "45") (name "unconnected-(DD18-NC-Pad14)") (class "Default")
      (node (ref "DD18") (pin "14") (pinfunction "NC_14") (pintype "tri_state+no_connect"))
    )
    (net (code "46") (name "unconnected-(DD19-D-Pad6)") (class "Default")
      (node (ref "DD19") (pin "6") (pinfunction "D_6") (pintype "input+no_connect"))
    )
    (net (code "47") (name "unconnected-(DD19-NC-Pad7)") (class "Default")
      (node (ref "DD19") (pin "7") (pinfunction "NC_7") (pintype "power_in+no_connect"))
    )
    (net (code "48") (name "unconnected-(DD19-NC-Pad10)") (class "Default")
      (node (ref "DD19") (pin "10") (pinfunction "NC_10") (pintype "passive+no_connect"))
    )
    (net (code "49") (name "unconnected-(DD19-NC-Pad11)") (class "Default")
      (node (ref "DD19") (pin "11") (pinfunction "NC_11") (pintype "tri_state+no_connect"))
    )
    (net (code "50") (name "unconnected-(DD19-NC-Pad14)") (class "Default")
      (node (ref "DD19") (pin "14") (pinfunction "NC_14") (pintype "tri_state+no_connect"))
    )
    (net (code "51") (name "unconnected-(DD20-D-Pad6)") (class "Default")
      (node (ref "DD20") (pin "6") (pinfunction "D_6") (pintype "input+no_connect"))
    )
    (net (code "52") (name "unconnected-(DD20-NC-Pad7)") (class "Default")
      (node (ref "DD20") (pin "7") (pinfunction "NC_7") (pintype "power_in+no_connect"))
    )
    (net (code "53") (name "unconnected-(DD20-NC-Pad10)") (class "Default")
      (node (ref "DD20") (pin "10") (pinfunction "NC_10") (pintype "passive+no_connect"))
    )
    (net (code "54") (name "unconnected-(DD20-NC-Pad11)") (class "Default")
      (node (ref "DD20") (pin "11") (pinfunction "NC_11") (pintype "tri_state+no_connect"))
    )
    (net (code "55") (name "unconnected-(DD20-NC-Pad14)") (class "Default")
      (node (ref "DD20") (pin "14") (pinfunction "NC_14") (pintype "tri_state+no_connect"))
    )
    (net (code "56") (name "unconnected-(DD21-NC-Pad7)") (class "Default")
      (node (ref "DD21") (pin "7") (pinfunction "NC_7") (pintype "power_in+no_connect"))
    )
    (net (code "57") (name "unconnected-(DD21-NC-Pad10)") (class "Default")
      (node (ref "DD21") (pin "10") (pinfunction "NC_10") (pintype "passive+no_connect"))
    )
    (net (code "58") (name "unconnected-(DD22-NC-Pad7)") (class "Default")
      (node (ref "DD22") (pin "7") (pinfunction "NC_7") (pintype "power_in+no_connect"))
    )
    (net (code "59") (name "unconnected-(DD22-NC-Pad10)") (class "Default")
      (node (ref "DD22") (pin "10") (pinfunction "NC_10") (pintype "passive+no_connect"))
    )
    (net (code "60") (name "unconnected-(DD22-NC-Pad11)") (class "Default")
      (node (ref "DD22") (pin "11") (pinfunction "NC_11") (pintype "tri_state+no_connect"))
    )
    (net (code "61") (name "unconnected-(DD22-NC-Pad14)") (class "Default")
      (node (ref "DD22") (pin "14") (pinfunction "NC_14") (pintype "tri_state+no_connect"))
    )
  )
)
